# GateDriverandMosfets.net
KiCad netlist of a schematic drawn in Altium Designer
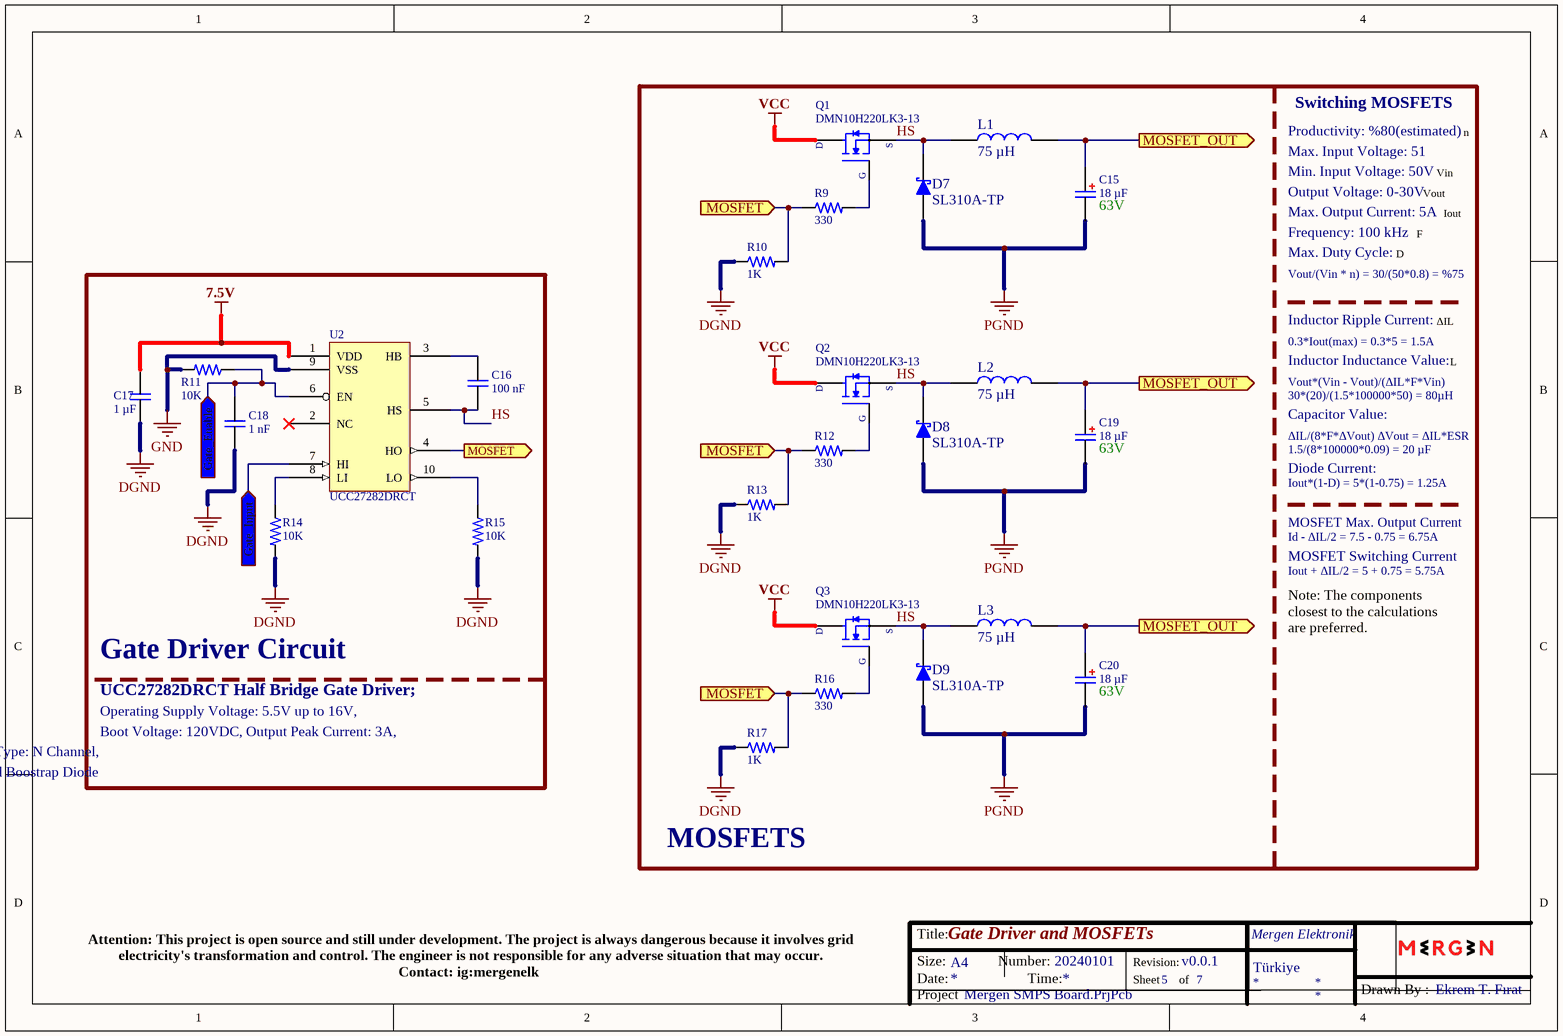
[diagram p0: GateDriverandMosfets.SchDoc]

(export (version "E")
  (design (tool "Eeschema 10.0.6"))
  (components
    (comp (ref "C15")
      (value "18 µF")
      (footprint "MergenElektronik_Capacitors_AluminumElectrolytics_THTs_8x7MM")
      (description "Mergen Elektronik- Capacitors - Aluminum Electrolytics - THTs - 63SXE18M")
      (fields
        (field (name "MANUFACTURER") "Panasonic")
        (field (name "TOLERANCE") "±20%")
        (field (name "VOLTAGE RATED") "63V")
      )
      (libsource (lib "MergenElektronik_Capacitors_AluminumElectrolytics_THTs") (part "MergenElektronik_Capacitors_AluminumElectrolytics_SMDs_63SXE18M"))
    )
    (comp (ref "C16")
      (value "100 nF")
      (footprint "MergenElektronik_Capacitors_Ceramics_SMDs_0603_S_NS")
      (description "Mergen Elektronik - Capacitors - Ceramics - SMDs - 0603 - 100 nF - 100V")
      (fields (field (name "MANUFACTURER") "Samsung") (field (name "TOLERANCE") "±10%"))
      (libsource (lib "MergenElektronik_Capacitors_Ceramics_SMDs") (part "MergenElektronik_Capacitors_Ceramic_SMDs_100nF_100V"))
    )
    (comp (ref "C17")
      (value "1 µF")
      (footprint "MergenElektronik_Capacitors_Ceramics_SMDs_1206_S_NS")
      (description "Mergen Elektronik - Capacitors - Ceramics - SMDs - 1206 - 1 µF - 100V")
      (fields (field (name "MANUFACTURER") "Samsung") (field (name "TOLERANCE") "±10%"))
      (libsource (lib "MergenElektronik_Capacitors_Ceramics_SMDs") (part "MergenElektronik_Capacitors_Ceramic_SMDs_1µF_100V"))
    )
    (comp (ref "C18")
      (value "1 nF")
      (footprint "MergenElektronik_Capacitors_Ceramics_SMDs_0402_S_NS")
      (description "Mergen Elektronik - Capacitors - Ceramics - SMDs - 0402 - 1 nF - 50V")
      (fields (field (name "MANUFACTURER") "Murata Electronics") (field (name "TOLERANCE") "±5%"))
      (libsource (lib "MergenElektronik_Capacitors_Ceramics_SMDs") (part "MergenElektronik_Capacitors_Ceramic_SMDs_1nF_50V"))
    )
    (comp (ref "C19")
      (value "18 µF")
      (footprint "MergenElektronik_Capacitors_AluminumElectrolytics_THTs_8x7MM")
      (description "Mergen Elektronik- Capacitors - Aluminum Electrolytics - THTs - 63SXE18M")
      (fields
        (field (name "MANUFACTURER") "Panasonic")
        (field (name "TOLERANCE") "±20%")
        (field (name "VOLTAGE RATED") "63V")
      )
      (libsource (lib "MergenElektronik_Capacitors_AluminumElectrolytics_THTs") (part "MergenElektronik_Capacitors_AluminumElectrolytics_SMDs_63SXE18M"))
    )
    (comp (ref "C20")
      (value "18 µF")
      (footprint "MergenElektronik_Capacitors_AluminumElectrolytics_THTs_8x7MM")
      (description "Mergen Elektronik- Capacitors - Aluminum Electrolytics - THTs - 63SXE18M")
      (fields
        (field (name "MANUFACTURER") "Panasonic")
        (field (name "TOLERANCE") "±20%")
        (field (name "VOLTAGE RATED") "63V")
      )
      (libsource (lib "MergenElektronik_Capacitors_AluminumElectrolytics_THTs") (part "MergenElektronik_Capacitors_AluminumElectrolytics_SMDs_63SXE18M"))
    )
    (comp (ref "D7")
      (value "SL310A-TP")
      (footprint "MergenElektronik_Diodes_SchottkyDiodes_DO-214AC (SMA)")
      (description "Mergen Elektronik - Diodes - Schottky Diodes - SL310A-TP")
      (fields (field (name "MANUFACTURER") "Micro Commercial Co"))
      (libsource (lib "MergenElektronik_Diodes_SchottkyDiodes") (part "MergenElektronik_Diodes_SchottkyDiodes_SL310A-TP"))
    )
    (comp (ref "D8")
      (value "SL310A-TP")
      (footprint "MergenElektronik_Diodes_SchottkyDiodes_DO-214AC (SMA)")
      (description "Mergen Elektronik - Diodes - Schottky Diodes - SL310A-TP")
      (fields (field (name "MANUFACTURER") "Micro Commercial Co"))
      (libsource (lib "MergenElektronik_Diodes_SchottkyDiodes") (part "MergenElektronik_Diodes_SchottkyDiodes_SL310A-TP"))
    )
    (comp (ref "D9")
      (value "SL310A-TP")
      (footprint "MergenElektronik_Diodes_SchottkyDiodes_DO-214AC (SMA)")
      (description "Mergen Elektronik - Diodes - Schottky Diodes - SL310A-TP")
      (fields (field (name "MANUFACTURER") "Micro Commercial Co"))
      (libsource (lib "MergenElektronik_Diodes_SchottkyDiodes") (part "MergenElektronik_Diodes_SchottkyDiodes_SL310A-TP"))
    )
    (comp (ref "L1")
      (value "75 µH")
      (footprint "MergenElektronik_Inductors_PowerInductors_SMDs_8x8x4mm_Shielded")
      (description "Mergen Elektronik - Inductors - Power Inductors - SMDs - 8x8mm  75-µh - 1.2A")
      (fields (field (name "MANUFACTURER") "Abracon LLC"))
      (libsource (lib "MergenElektronik_Inductors_PowerInductors_SMDs") (part "MergenElektronik_Inductors_PowerInductors_SMDs_ASPI-8040S-750M-T"))
    )
    (comp (ref "L2")
      (value "75 µH")
      (footprint "MergenElektronik_Inductors_PowerInductors_SMDs_8x8x4mm_Shielded")
      (description "Mergen Elektronik - Inductors - Power Inductors - SMDs - 8x8mm  75-µh - 1.2A")
      (fields (field (name "MANUFACTURER") "Abracon LLC"))
      (libsource (lib "MergenElektronik_Inductors_PowerInductors_SMDs") (part "MergenElektronik_Inductors_PowerInductors_SMDs_ASPI-8040S-750M-T"))
    )
    (comp (ref "L3")
      (value "75 µH")
      (footprint "MergenElektronik_Inductors_PowerInductors_SMDs_8x8x4mm_Shielded")
      (description "Mergen Elektronik - Inductors - Power Inductors - SMDs - 8x8mm  75-µh - 1.2A")
      (fields (field (name "MANUFACTURER") "Abracon LLC"))
      (libsource (lib "MergenElektronik_Inductors_PowerInductors_SMDs") (part "MergenElektronik_Inductors_PowerInductors_SMDs_ASPI-8040S-750M-T"))
    )
    (comp (ref "Q1")
      (value "DMN10H220LK3-13")
      (footprint "MergenElektronik_Transistors_Mosfets_TO-252-3(DPAK)")
      (description "Mergen Elektronik - Transistors - Mosfets - DMN10H220LK3-13")
      (fields (field (name "MANUFACTURER") "Diodes Incorporated"))
      (libsource (lib "MergenElektronik_Transistors_Mosfets") (part "MergenElektronik_Transistors_Mosfets_DMN10H220LK3-13"))
    )
    (comp (ref "Q2")
      (value "DMN10H220LK3-13")
      (footprint "MergenElektronik_Transistors_Mosfets_TO-252-3(DPAK)")
      (description "Mergen Elektronik - Transistors - Mosfets - DMN10H220LK3-13")
      (fields (field (name "MANUFACTURER") "Diodes Incorporated"))
      (libsource (lib "MergenElektronik_Transistors_Mosfets") (part "MergenElektronik_Transistors_Mosfets_DMN10H220LK3-13"))
    )
    (comp (ref "Q3")
      (value "DMN10H220LK3-13")
      (footprint "MergenElektronik_Transistors_Mosfets_TO-252-3(DPAK)")
      (description "Mergen Elektronik - Transistors - Mosfets - DMN10H220LK3-13")
      (fields (field (name "MANUFACTURER") "Diodes Incorporated"))
      (libsource (lib "MergenElektronik_Transistors_Mosfets") (part "MergenElektronik_Transistors_Mosfets_DMN10H220LK3-13"))
    )
    (comp (ref "R9")
      (value "330")
      (footprint "MergenElektronik_Resistors_ChipResistors_0603_S_NS")
      (description "Mergen Elektronik - Resistors - Chip Resistors - 0603 - 330R")
      (fields (field (name "MANUFACTURER") "Stackpole") (field (name "POWER") "1/10W"))
      (libsource (lib "MergenElektronik_Resistors_ChipResistors") (part "MergenElektronik_Resistors_ChipResistors_0603_330R"))
    )
    (comp (ref "R10")
      (value "1K")
      (footprint "MergenElektronik_Resistors_ChipResistors_0603_S_NS")
      (description "Mergen Elektronik - Resistors - Chip Resistors - 0603 - 1K")
      (fields (field (name "MANUFACTURER") "Stackpole") (field (name "POWER") "1/10W"))
      (libsource (lib "MergenElektronik_Resistors_ChipResistors") (part "MergenElektronik_Resistors_ChipResistors_0603_1K"))
    )
    (comp (ref "R11")
      (value "10K")
      (footprint "MergenElektronik_Resistors_ChipResistors_0603_S_NS")
      (description "Mergen Elektronik - Resistors - Chip Resistors - 0603 - 10K")
      (fields (field (name "MANUFACTURER") "Stackpole") (field (name "POWER") "1/10W"))
      (libsource (lib "MergenElektronik_Resistors_ChipResistors") (part "MergenElektronik_Resistors_ChipResistors_0603_10K"))
    )
    (comp (ref "R12")
      (value "330")
      (footprint "MergenElektronik_Resistors_ChipResistors_0603_S_NS")
      (description "Mergen Elektronik - Resistors - Chip Resistors - 0603 - 330R")
      (fields (field (name "MANUFACTURER") "Stackpole") (field (name "POWER") "1/10W"))
      (libsource (lib "MergenElektronik_Resistors_ChipResistors") (part "MergenElektronik_Resistors_ChipResistors_0603_330R"))
    )
    (comp (ref "R13")
      (value "1K")
      (footprint "MergenElektronik_Resistors_ChipResistors_0603_S_NS")
      (description "Mergen Elektronik - Resistors - Chip Resistors - 0603 - 1K")
      (fields (field (name "MANUFACTURER") "Stackpole") (field (name "POWER") "1/10W"))
      (libsource (lib "MergenElektronik_Resistors_ChipResistors") (part "MergenElektronik_Resistors_ChipResistors_0603_1K"))
    )
    (comp (ref "R14")
      (value "10K")
      (footprint "MergenElektronik_Resistors_ChipResistors_0603_S_NS")
      (description "Mergen Elektronik - Resistors - Chip Resistors - 0603 - 10K")
      (fields (field (name "MANUFACTURER") "Stackpole") (field (name "POWER") "1/10W"))
      (libsource (lib "MergenElektronik_Resistors_ChipResistors") (part "MergenElektronik_Resistors_ChipResistors_0603_10K"))
    )
    (comp (ref "R15")
      (value "10K")
      (footprint "MergenElektronik_Resistors_ChipResistors_0603_S_NS")
      (description "Mergen Elektronik - Resistors - Chip Resistors - 0603 - 10K")
      (fields (field (name "MANUFACTURER") "Stackpole") (field (name "POWER") "1/10W"))
      (libsource (lib "MergenElektronik_Resistors_ChipResistors") (part "MergenElektronik_Resistors_ChipResistors_0603_10K"))
    )
    (comp (ref "R16")
      (value "330")
      (footprint "MergenElektronik_Resistors_ChipResistors_0603_S_NS")
      (description "Mergen Elektronik - Resistors - Chip Resistors - 0603 - 330R")
      (fields (field (name "MANUFACTURER") "Stackpole") (field (name "POWER") "1/10W"))
      (libsource (lib "MergenElektronik_Resistors_ChipResistors") (part "MergenElektronik_Resistors_ChipResistors_0603_330R"))
    )
    (comp (ref "R17")
      (value "1K")
      (footprint "MergenElektronik_Resistors_ChipResistors_0603_S_NS")
      (description "Mergen Elektronik - Resistors - Chip Resistors - 0603 - 1K")
      (fields (field (name "MANUFACTURER") "Stackpole") (field (name "POWER") "1/10W"))
      (libsource (lib "MergenElektronik_Resistors_ChipResistors") (part "MergenElektronik_Resistors_ChipResistors_0603_1K"))
    )
    (comp (ref "U2")
      (value "UCC27282DRCT")
      (footprint "MergenElektronik_Logics_GateDrivers_10VSON")
      (description "Mergen Elektronik - Logics - Gate Drivers - UCC27282DRCT")
      (fields (field (name "MANUFACTURER") "Texas Instruments"))
      (libsource (lib "MergenElektronik_Logics_GateDrivers") (part "MergenElektronik_Logics_GateDrivers_UCC27282DRCT"))
    )
  )
  (nets
    (net (code "1") (name "/Gate_Enable") (class "Default")
      (node (ref "C18") (pin "1") (pinfunction "1_1") (pintype "passive"))
      (node (ref "R11") (pin "1") (pinfunction "1_1") (pintype "passive"))
      (node (ref "U2") (pin "6") (pinfunction "EN_6") (pintype "passive"))
    )
    (net (code "2") (name "/Gate_Input") (class "Default")
      (node (ref "U2") (pin "7") (pinfunction "HI_7") (pintype "input"))
    )
    (net (code "3") (name "/HS") (class "Default")
      (node (ref "C16") (pin "2") (pinfunction "2_2") (pintype "passive"))
      (node (ref "D7") (pin "2") (pinfunction "KATOT_2") (pintype "passive"))
      (node (ref "D8") (pin "2") (pinfunction "KATOT_2") (pintype "passive"))
      (node (ref "D9") (pin "2") (pinfunction "KATOT_2") (pintype "passive"))
      (node (ref "L1") (pin "1") (pinfunction "1_1") (pintype "passive"))
      (node (ref "L2") (pin "1") (pinfunction "1_1") (pintype "passive"))
      (node (ref "L3") (pin "1") (pinfunction "1_1") (pintype "passive"))
      (node (ref "Q1") (pin "2") (pinfunction "Source_2") (pintype "passive"))
      (node (ref "Q2") (pin "2") (pinfunction "Source_2") (pintype "passive"))
      (node (ref "Q3") (pin "2") (pinfunction "Source_2") (pintype "passive"))
      (node (ref "U2") (pin "5") (pinfunction "HS_5") (pintype "power_in"))
    )
    (net (code "4") (name "/MOSFET") (class "Default")
      (node (ref "R10") (pin "2") (pinfunction "2_2") (pintype "passive"))
      (node (ref "R12") (pin "1") (pinfunction "1_1") (pintype "passive"))
      (node (ref "R13") (pin "2") (pinfunction "2_2") (pintype "passive"))
      (node (ref "R16") (pin "1") (pinfunction "1_1") (pintype "passive"))
      (node (ref "R17") (pin "2") (pinfunction "2_2") (pintype "passive"))
      (node (ref "R9") (pin "1") (pinfunction "1_1") (pintype "passive"))
      (node (ref "U2") (pin "4") (pinfunction "HO_4") (pintype "output"))
    )
    (net (code "5") (name "/MOSFET_OUT") (class "Default")
      (node (ref "C15") (pin "ANOT") (pinfunction "2_ANOT") (pintype "passive"))
      (node (ref "C19") (pin "ANOT") (pinfunction "2_ANOT") (pintype "passive"))
      (node (ref "C20") (pin "ANOT") (pinfunction "2_ANOT") (pintype "passive"))
      (node (ref "L1") (pin "2") (pinfunction "2_2") (pintype "passive"))
      (node (ref "L2") (pin "2") (pinfunction "2_2") (pintype "passive"))
      (node (ref "L3") (pin "2") (pinfunction "2_2") (pintype "passive"))
    )
    (net (code "6") (name "7.5V") (class "Default")
      (node (ref "C17") (pin "1") (pinfunction "1_1") (pintype "passive"))
      (node (ref "U2") (pin "1") (pinfunction "VDD_1") (pintype "power_in"))
    )
    (net (code "7") (name "DGND") (class "Default")
      (node (ref "C17") (pin "2") (pinfunction "2_2") (pintype "passive"))
      (node (ref "C18") (pin "2") (pinfunction "2_2") (pintype "passive"))
      (node (ref "R10") (pin "1") (pinfunction "1_1") (pintype "passive"))
      (node (ref "R13") (pin "1") (pinfunction "1_1") (pintype "passive"))
      (node (ref "R14") (pin "2") (pinfunction "2_2") (pintype "passive"))
      (node (ref "R15") (pin "2") (pinfunction "2_2") (pintype "passive"))
      (node (ref "R17") (pin "1") (pinfunction "1_1") (pintype "passive"))
    )
    (net (code "8") (name "GND") (class "Default")
      (node (ref "R11") (pin "2") (pinfunction "2_2") (pintype "passive"))
      (node (ref "U2") (pin "9") (pinfunction "VSS_9") (pintype "power_in"))
    )
    (net (code "9") (name "Net-(Q1-Gate)") (class "Default")
      (node (ref "Q1") (pin "1") (pinfunction "Gate_1") (pintype "passive"))
      (node (ref "R9") (pin "2") (pinfunction "2_2") (pintype "passive"))
    )
    (net (code "10") (name "Net-(Q2-Gate)") (class "Default")
      (node (ref "Q2") (pin "1") (pinfunction "Gate_1") (pintype "passive"))
      (node (ref "R12") (pin "2") (pinfunction "2_2") (pintype "passive"))
    )
    (net (code "11") (name "Net-(Q3-Gate)") (class "Default")
      (node (ref "Q3") (pin "1") (pinfunction "Gate_1") (pintype "passive"))
      (node (ref "R16") (pin "2") (pinfunction "2_2") (pintype "passive"))
    )
    (net (code "12") (name "Net-(U2-HB)") (class "Default")
      (node (ref "C16") (pin "1") (pinfunction "1_1") (pintype "passive"))
      (node (ref "U2") (pin "3") (pinfunction "HB_3") (pintype "power_in"))
    )
    (net (code "13") (name "Net-(U2-LI)") (class "Default")
      (node (ref "R14") (pin "1") (pinfunction "1_1") (pintype "passive"))
      (node (ref "U2") (pin "8") (pinfunction "LI_8") (pintype "input"))
    )
    (net (code "14") (name "Net-(U2-LO)") (class "Default")
      (node (ref "R15") (pin "1") (pinfunction "1_1") (pintype "passive"))
      (node (ref "U2") (pin "10") (pinfunction "LO_10") (pintype "output"))
    )
    (net (code "15") (name "PGND") (class "Default")
      (node (ref "C15") (pin "KATOT") (pinfunction "1_KATOT") (pintype "passive"))
      (node (ref "C19") (pin "KATOT") (pinfunction "1_KATOT") (pintype "passive"))
      (node (ref "C20") (pin "KATOT") (pinfunction "1_KATOT") (pintype "passive"))
      (node (ref "D7") (pin "1") (pinfunction "ANOT_1") (pintype "passive"))
      (node (ref "D8") (pin "1") (pinfunction "ANOT_1") (pintype "passive"))
      (node (ref "D9") (pin "1") (pinfunction "ANOT_1") (pintype "passive"))
    )
    (net (code "16") (name "VCC") (class "Default")
      (node (ref "Q1") (pin "3") (pinfunction "Drain_3") (pintype "passive"))
      (node (ref "Q2") (pin "3") (pinfunction "Drain_3") (pintype "passive"))
      (node (ref "Q3") (pin "3") (pinfunction "Drain_3") (pintype "passive"))
    )
    (net (code "17") (name "unconnected-(U2-NC-Pad2)") (class "Default")
      (node (ref "U2") (pin "2") (pinfunction "NC_2") (pintype "passive+no_connect"))
    )
  )
)
